# BatchD.net
KiCad netlist of a schematic drawn in EAGLE
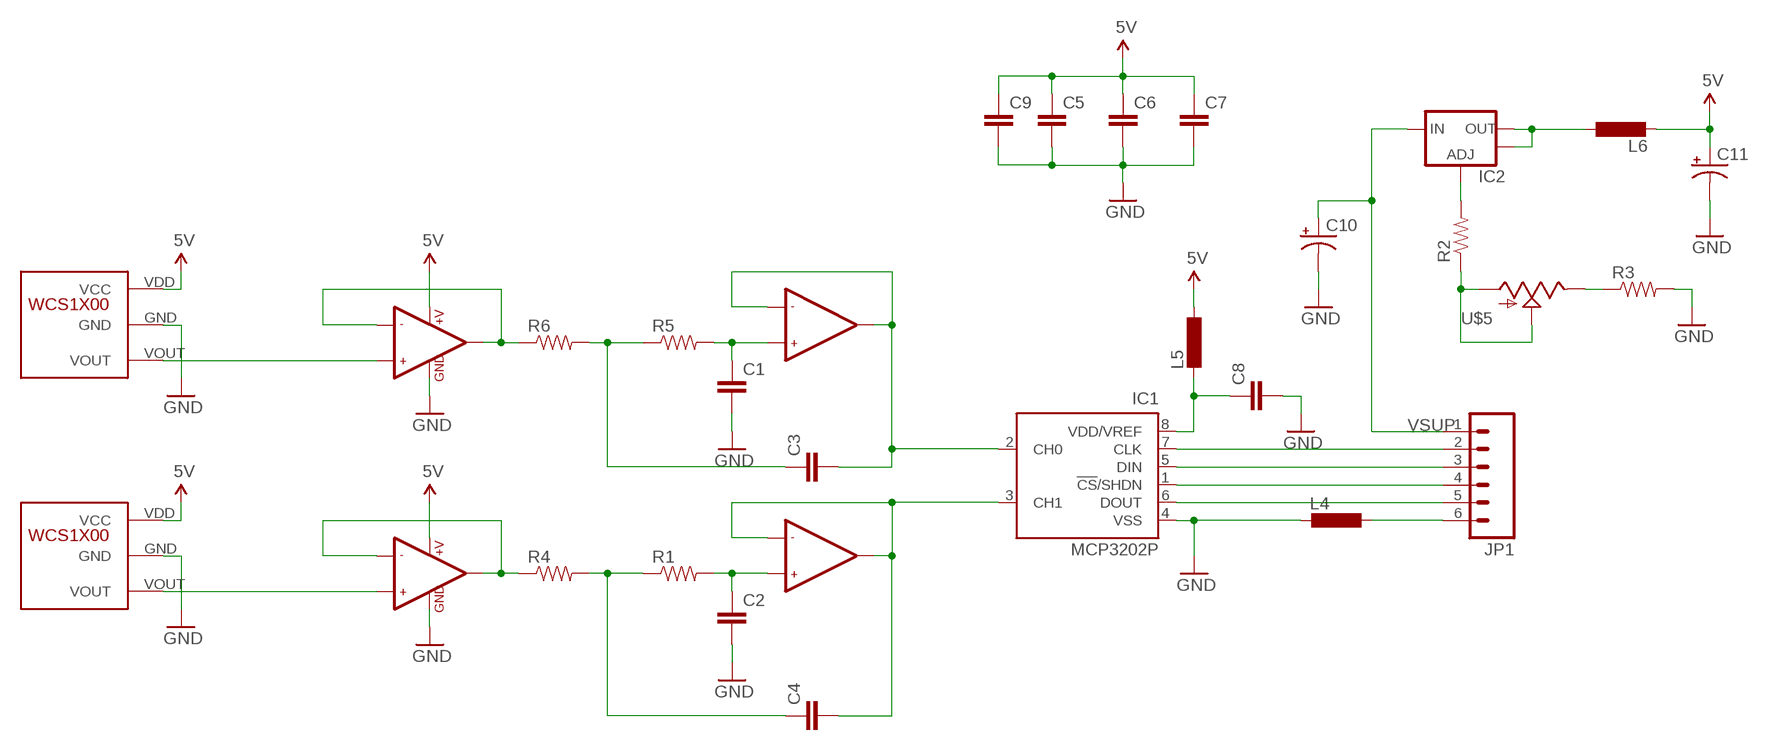
[diagram p0: schematic, sheet 1]

(export (version "E")
  (design (tool "Eeschema 10.0.6"))
  (components
    (comp (ref "C1")
      (value "CAP1206")
      (footprint "eagle-import:1206")
      (libsource (lib "eagle-import") (part "CAP1206"))
    )
    (comp (ref "C2")
      (value "CAP1206")
      (footprint "eagle-import:1206")
      (libsource (lib "eagle-import") (part "CAP1206"))
    )
    (comp (ref "C3")
      (value "CAP1206")
      (footprint "eagle-import:1206")
      (libsource (lib "eagle-import") (part "CAP1206"))
    )
    (comp (ref "C4")
      (value "CAP1206")
      (footprint "eagle-import:1206")
      (libsource (lib "eagle-import") (part "CAP1206"))
    )
    (comp (ref "C5")
      (value "CAP1206")
      (footprint "eagle-import:1206")
      (libsource (lib "eagle-import") (part "CAP1206"))
    )
    (comp (ref "C6")
      (value "CAP1206")
      (footprint "eagle-import:1206")
      (libsource (lib "eagle-import") (part "CAP1206"))
    )
    (comp (ref "C7")
      (value "CAP1206")
      (footprint "eagle-import:1206")
      (libsource (lib "eagle-import") (part "CAP1206"))
    )
    (comp (ref "C8")
      (value "CAP1206")
      (footprint "eagle-import:1206")
      (libsource (lib "eagle-import") (part "CAP1206"))
    )
    (comp (ref "C9")
      (value "CAP1206")
      (footprint "eagle-import:1206")
      (libsource (lib "eagle-import") (part "CAP1206"))
    )
    (comp (ref "C10")
      (value "CAP_POLPTH4")
      (footprint "eagle-import:CPOL-RADIAL-1000UF-25V")
      (libsource (lib "eagle-import") (part "CAP_POLPTH4"))
    )
    (comp (ref "C11")
      (value "CAP_POLPTH1")
      (footprint "eagle-import:CPOL-RADIAL-100UF-25V")
      (libsource (lib "eagle-import") (part "CAP_POLPTH1"))
    )
    (comp (ref "IC1")
      (value "MCP3202P")
      (footprint "eagle-import:DIL8")
      (fields (field (name "MF") "MICROCHIP") (field (name "MPN") "MCP3202-CI/P"))
      (libsource (lib "eagle-import") (part "MCP3202P"))
    )
    (comp (ref "IC2")
      (value "V_REG_LM1117SOT223")
      (footprint "eagle-import:SOT223")
      (libsource (lib "eagle-import") (part "V_REG_LM1117SOT223"))
    )
    (comp (ref "JP1")
      (value "M06LONGPADS")
      (footprint "eagle-import:1X06_LONGPADS")
      (libsource (lib "eagle-import") (part "M06LONGPADS"))
    )
    (comp (ref "L4")
      (value "L-EU0204V")
      (footprint "eagle-import:0204V")
      (libsource (lib "eagle-import") (part "L-EU0204V"))
    )
    (comp (ref "L5")
      (value "L-EU0204V")
      (footprint "eagle-import:0204V")
      (libsource (lib "eagle-import") (part "L-EU0204V"))
    )
    (comp (ref "L6")
      (value "L-EU0204V")
      (footprint "eagle-import:0204V")
      (libsource (lib "eagle-import") (part "L-EU0204V"))
    )
    (comp (ref "R1")
      (value "RESISTOR1206")
      (footprint "eagle-import:1206")
      (libsource (lib "eagle-import") (part "RESISTOR1206"))
    )
    (comp (ref "R2")
      (value "RESISTOR1206")
      (footprint "eagle-import:1206")
      (libsource (lib "eagle-import") (part "RESISTOR1206"))
    )
    (comp (ref "R3")
      (value "RESISTOR1206")
      (footprint "eagle-import:1206")
      (libsource (lib "eagle-import") (part "RESISTOR1206"))
    )
    (comp (ref "R4")
      (value "RESISTOR1206")
      (footprint "eagle-import:1206")
      (libsource (lib "eagle-import") (part "RESISTOR1206"))
    )
    (comp (ref "R5")
      (value "RESISTOR1206")
      (footprint "eagle-import:1206")
      (libsource (lib "eagle-import") (part "RESISTOR1206"))
    )
    (comp (ref "R6")
      (value "RESISTOR1206")
      (footprint "eagle-import:1206")
      (libsource (lib "eagle-import") (part "RESISTOR1206"))
    )
    (comp (ref "U$1")
      (value "LMV358")
      (footprint "eagle-import:SO08")
      (libsource (lib "eagle-import") (part "LMV358"))
    )
    (comp (ref "U$2")
      (value "LMV358")
      (footprint "eagle-import:SO08")
      (libsource (lib "eagle-import") (part "LMV358"))
    )
    (comp (ref "U$3")
      (value "WCS1X00")
      (footprint "eagle-import:WCS1X00")
      (libsource (lib "eagle-import") (part "WCS1X00"))
    )
    (comp (ref "U$4")
      (value "WCS1X00")
      (footprint "eagle-import:WCS1X00")
      (libsource (lib "eagle-import") (part "WCS1X00"))
    )
    (comp (ref "U$5")
      (value "POTTRIM")
      (footprint "eagle-import:TRIM_POT")
      (libsource (lib "eagle-import") (part "POTTRIM"))
    )
  )
  (nets
    (net (code "1") (name "/VSUP") (class "Default")
      (node (ref "C10") (pin "1") (pinfunction "+_1") (pintype "passive"))
      (node (ref "IC2") (pin "3") (pinfunction "IN_3") (pintype "input"))
      (node (ref "JP1") (pin "1") (pinfunction "1_1") (pintype "passive"))
    )
    (net (code "2") (name "5V") (class "Default")
      (node (ref "C11") (pin "1") (pinfunction "+_1") (pintype "passive"))
      (node (ref "C5") (pin "1") (pinfunction "1_1") (pintype "passive"))
      (node (ref "C6") (pin "1") (pinfunction "1_1") (pintype "passive"))
      (node (ref "C7") (pin "1") (pinfunction "1_1") (pintype "passive"))
      (node (ref "C9") (pin "1") (pinfunction "1_1") (pintype "passive"))
      (node (ref "L5") (pin "1") (pinfunction "1_1") (pintype "passive"))
      (node (ref "L6") (pin "2") (pinfunction "2_2") (pintype "passive"))
      (node (ref "U$1") (pin "8") (pinfunction "+V_8") (pintype "power_in"))
      (node (ref "U$2") (pin "8") (pinfunction "+V_8") (pintype "power_in"))
      (node (ref "U$3") (pin "VDD") (pinfunction "VCC_VDD") (pintype "bidirectional"))
      (node (ref "U$4") (pin "VDD") (pinfunction "VCC_VDD") (pintype "bidirectional"))
    )
    (net (code "3") (name "GND") (class "Default")
      (node (ref "C1") (pin "2") (pinfunction "2_2") (pintype "passive"))
      (node (ref "C10") (pin "2") (pinfunction "-_2") (pintype "passive"))
      (node (ref "C11") (pin "2") (pinfunction "-_2") (pintype "passive"))
      (node (ref "C2") (pin "2") (pinfunction "2_2") (pintype "passive"))
      (node (ref "C5") (pin "2") (pinfunction "2_2") (pintype "passive"))
      (node (ref "C6") (pin "2") (pinfunction "2_2") (pintype "passive"))
      (node (ref "C7") (pin "2") (pinfunction "2_2") (pintype "passive"))
      (node (ref "C8") (pin "2") (pinfunction "2_2") (pintype "passive"))
      (node (ref "C9") (pin "2") (pinfunction "2_2") (pintype "passive"))
      (node (ref "IC1") (pin "4") (pinfunction "VSS_4") (pintype "input"))
      (node (ref "L4") (pin "2") (pinfunction "2_2") (pintype "passive"))
      (node (ref "R3") (pin "2") (pinfunction "2_2") (pintype "passive"))
      (node (ref "U$1") (pin "4") (pinfunction "GND_4") (pintype "power_in"))
      (node (ref "U$2") (pin "4") (pinfunction "GND_4") (pintype "power_in"))
      (node (ref "U$3") (pin "GND") (pinfunction "GND_GND") (pintype "bidirectional"))
      (node (ref "U$4") (pin "GND") (pinfunction "GND_GND") (pintype "bidirectional"))
    )
    (net (code "4") (name "Net-(C3-Pad1)") (class "Default")
      (node (ref "C3") (pin "1") (pinfunction "1_1") (pintype "passive"))
      (node (ref "R5") (pin "1") (pinfunction "1_1") (pintype "passive"))
      (node (ref "R6") (pin "2") (pinfunction "2_2") (pintype "passive"))
    )
    (net (code "5") (name "Net-(C4-Pad1)") (class "Default")
      (node (ref "C4") (pin "1") (pinfunction "1_1") (pintype "passive"))
      (node (ref "R1") (pin "1") (pinfunction "1_1") (pintype "passive"))
      (node (ref "R4") (pin "2") (pinfunction "2_2") (pintype "passive"))
    )
    (net (code "6") (name "Net-(IC1-CH0)") (class "Default")
      (node (ref "C3") (pin "2") (pinfunction "2_2") (pintype "passive"))
      (node (ref "IC1") (pin "2") (pinfunction "CH0_2") (pintype "input"))
      (node (ref "U$1") (pin "6") (pinfunction "-IN2_6") (pintype "input"))
      (node (ref "U$1") (pin "7") (pinfunction "OUT2_7") (pintype "output"))
    )
    (net (code "7") (name "Net-(IC1-CH1)") (class "Default")
      (node (ref "C4") (pin "2") (pinfunction "2_2") (pintype "passive"))
      (node (ref "IC1") (pin "3") (pinfunction "CH1_3") (pintype "input"))
      (node (ref "U$2") (pin "6") (pinfunction "-IN2_6") (pintype "input"))
      (node (ref "U$2") (pin "7") (pinfunction "OUT2_7") (pintype "output"))
    )
    (net (code "8") (name "Net-(IC1-CLK)") (class "Default")
      (node (ref "IC1") (pin "7") (pinfunction "CLK_7") (pintype "input"))
      (node (ref "JP1") (pin "2") (pinfunction "2_2") (pintype "passive"))
    )
    (net (code "9") (name "Net-(IC1-DIN)") (class "Default")
      (node (ref "IC1") (pin "5") (pinfunction "DIN_5") (pintype "input"))
      (node (ref "JP1") (pin "3") (pinfunction "3_3") (pintype "passive"))
    )
    (net (code "10") (name "Net-(IC1-DOUT)") (class "Default")
      (node (ref "IC1") (pin "6") (pinfunction "DOUT_6") (pintype "input"))
      (node (ref "JP1") (pin "5") (pinfunction "5_5") (pintype "passive"))
    )
    (net (code "11") (name "Net-(IC1-VDD{slash}VREF)") (class "Default")
      (node (ref "C8") (pin "1") (pinfunction "1_1") (pintype "passive"))
      (node (ref "IC1") (pin "8") (pinfunction "VDD/VREF_8") (pintype "input"))
      (node (ref "L5") (pin "2") (pinfunction "2_2") (pintype "passive"))
    )
    (net (code "12") (name "Net-(IC1-~{CS}{slash}SHDN)") (class "Default")
      (node (ref "IC1") (pin "1") (pinfunction "~{CS}/SHDN_1") (pintype "input"))
      (node (ref "JP1") (pin "4") (pinfunction "4_4") (pintype "passive"))
    )
    (net (code "13") (name "Net-(IC2-ADJ)") (class "Default")
      (node (ref "IC2") (pin "1") (pinfunction "ADJ_1") (pintype "input"))
      (node (ref "R2") (pin "2") (pinfunction "2_2") (pintype "passive"))
    )
    (net (code "14") (name "Net-(IC2-OUT-Pad2)") (class "Default")
      (node (ref "IC2") (pin "2") (pinfunction "OUT_2") (pintype "output"))
      (node (ref "IC2") (pin "4") (pinfunction "OUT_4") (pintype "output"))
      (node (ref "L6") (pin "1") (pinfunction "1_1") (pintype "passive"))
    )
    (net (code "15") (name "Net-(JP1-Pad6)") (class "Default")
      (node (ref "JP1") (pin "6") (pinfunction "6_6") (pintype "passive"))
      (node (ref "L4") (pin "1") (pinfunction "1_1") (pintype "passive"))
    )
    (net (code "16") (name "Net-(U$1A-+IN1)") (class "Default")
      (node (ref "U$1") (pin "3") (pinfunction "+IN1_3") (pintype "input"))
      (node (ref "U$3") (pin "VOUT") (pinfunction "VOUT_VOUT") (pintype "bidirectional"))
    )
    (net (code "17") (name "Net-(U$1A--IN1)") (class "Default")
      (node (ref "R6") (pin "1") (pinfunction "1_1") (pintype "passive"))
      (node (ref "U$1") (pin "1") (pinfunction "OUT1_1") (pintype "output"))
      (node (ref "U$1") (pin "2") (pinfunction "-IN1_2") (pintype "input"))
    )
    (net (code "18") (name "Net-(U$1B-+IN2)") (class "Default")
      (node (ref "C1") (pin "1") (pinfunction "1_1") (pintype "passive"))
      (node (ref "R5") (pin "2") (pinfunction "2_2") (pintype "passive"))
      (node (ref "U$1") (pin "5") (pinfunction "+IN2_5") (pintype "input"))
    )
    (net (code "19") (name "Net-(U$2A-+IN1)") (class "Default")
      (node (ref "U$2") (pin "3") (pinfunction "+IN1_3") (pintype "input"))
      (node (ref "U$4") (pin "VOUT") (pinfunction "VOUT_VOUT") (pintype "bidirectional"))
    )
    (net (code "20") (name "Net-(U$2A--IN1)") (class "Default")
      (node (ref "R4") (pin "1") (pinfunction "1_1") (pintype "passive"))
      (node (ref "U$2") (pin "1") (pinfunction "OUT1_1") (pintype "output"))
      (node (ref "U$2") (pin "2") (pinfunction "-IN1_2") (pintype "input"))
    )
    (net (code "21") (name "Net-(U$2B-+IN2)") (class "Default")
      (node (ref "C2") (pin "1") (pinfunction "1_1") (pintype "passive"))
      (node (ref "R1") (pin "2") (pinfunction "2_2") (pintype "passive"))
      (node (ref "U$2") (pin "5") (pinfunction "+IN2_5") (pintype "input"))
    )
    (net (code "22") (name "Net-(U$5-A)") (class "Default")
      (node (ref "R2") (pin "1") (pinfunction "1_1") (pintype "passive"))
      (node (ref "U$5") (pin "1") (pinfunction "S_1") (pintype "passive"))
      (node (ref "U$5") (pin "3") (pinfunction "A_3") (pintype "passive"))
    )
    (net (code "23") (name "Net-(U$5-E)") (class "Default")
      (node (ref "R3") (pin "1") (pinfunction "1_1") (pintype "passive"))
      (node (ref "U$5") (pin "2") (pinfunction "E_2") (pintype "passive"))
    )
  )
)
